# yacc1buss.net
KiCad netlist of a schematic drawn in EAGLE
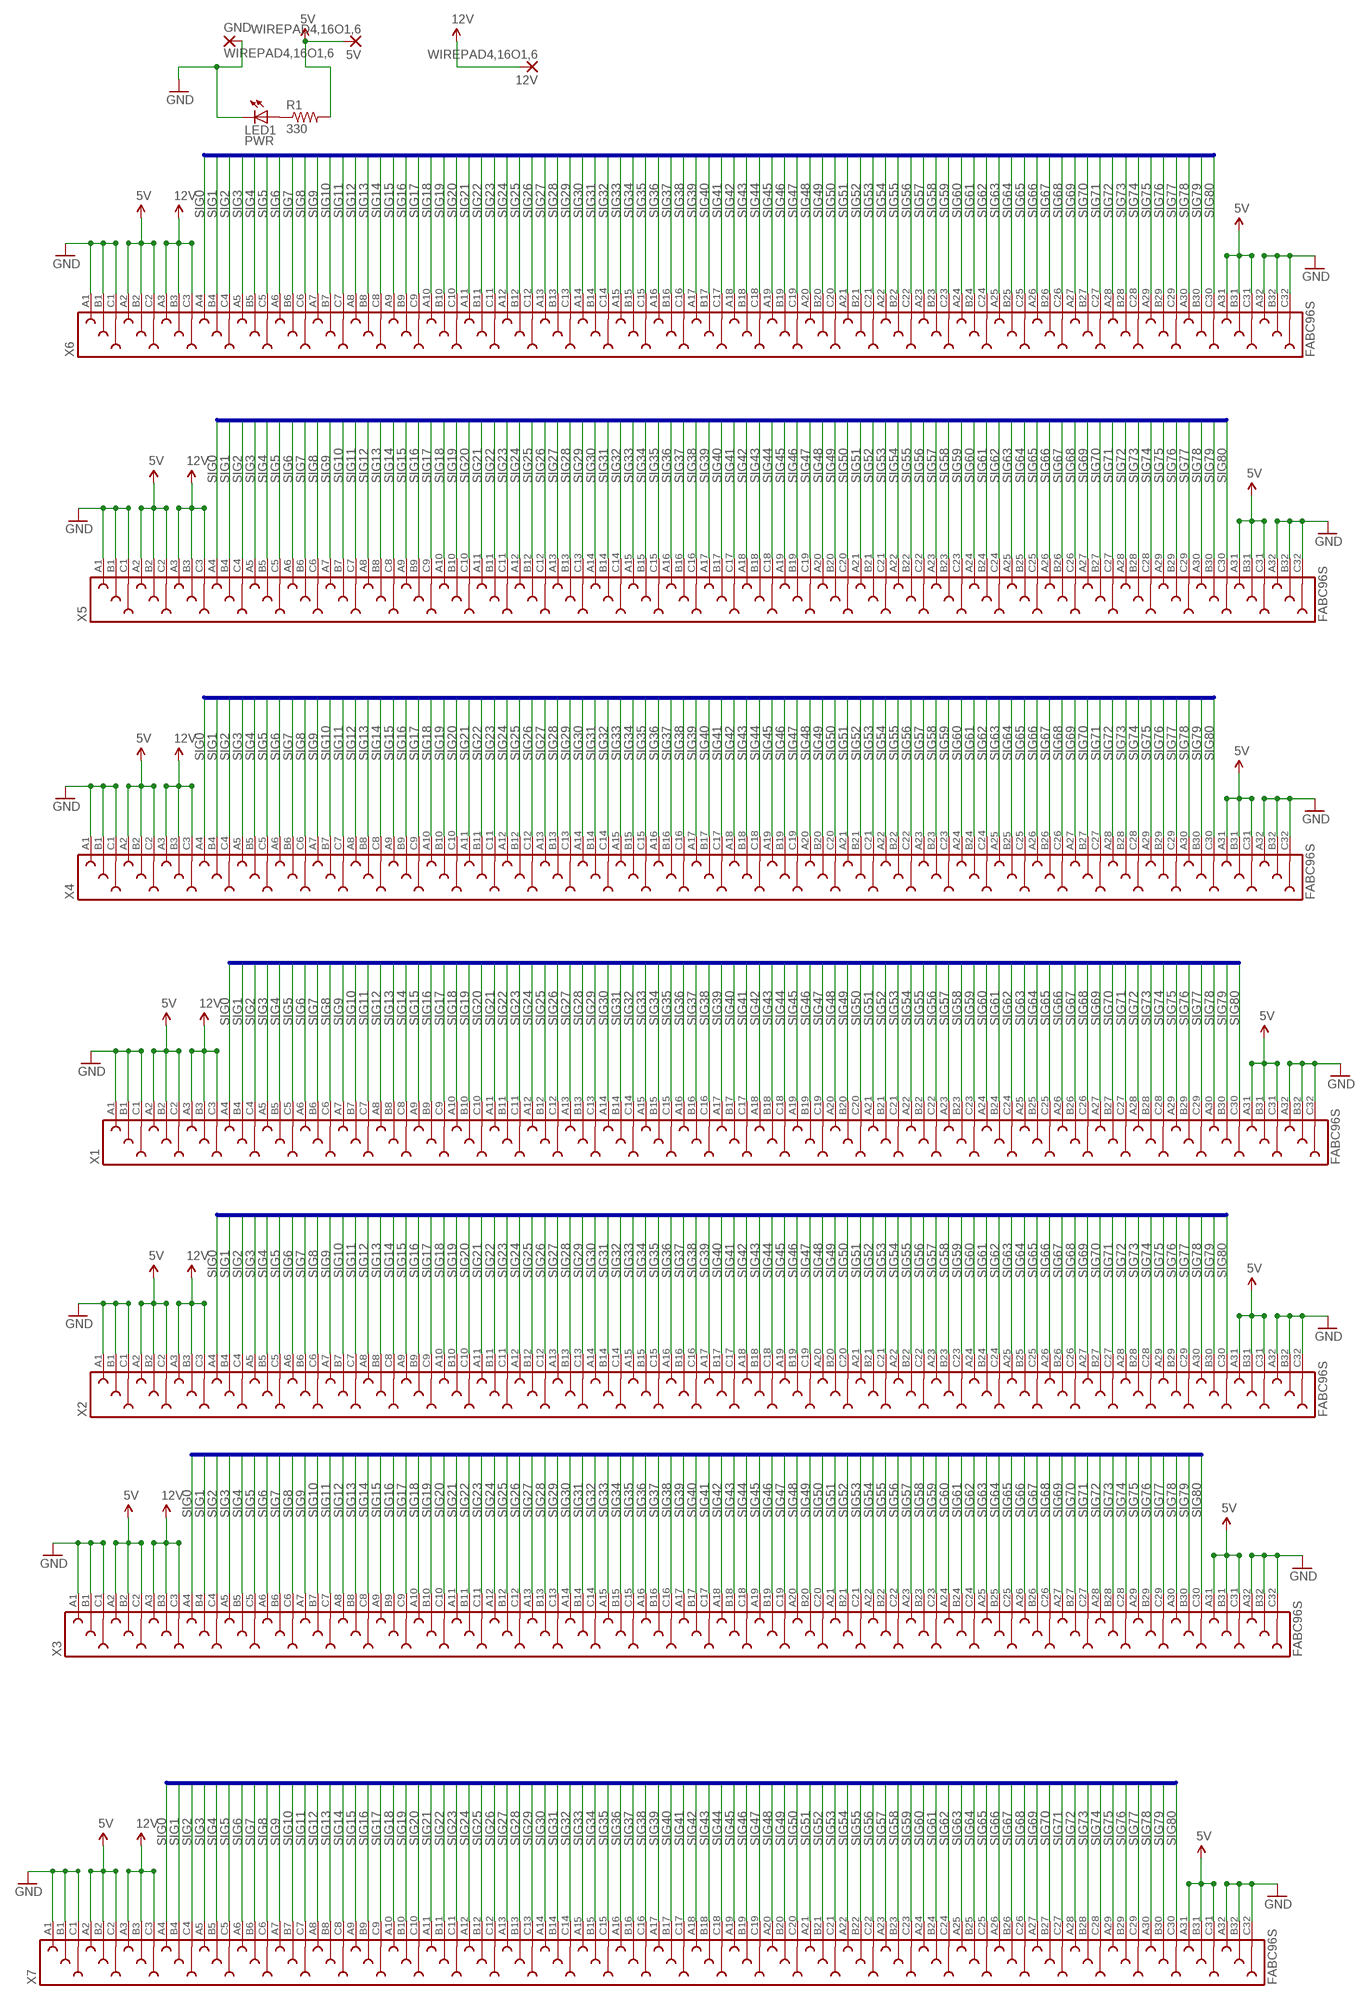
[diagram p0: schematic, sheet 1]

(export (version "E")
  (design (tool "Eeschema 10.0.6"))
  (components
    (comp (ref "5V")
      (value "WIREPAD4,16O1,6")
      (footprint "eagle-import:4,16O1,6")
      (libsource (lib "eagle-import") (part "WIREPAD4,16O1,6"))
    )
    (comp (ref "12V")
      (value "WIREPAD4,16O1,6")
      (footprint "eagle-import:4,16O1,6")
      (libsource (lib "eagle-import") (part "WIREPAD4,16O1,6"))
    )
    (comp (ref "GND")
      (value "WIREPAD4,16O1,6")
      (footprint "eagle-import:4,16O1,6")
      (libsource (lib "eagle-import") (part "WIREPAD4,16O1,6"))
    )
    (comp (ref "LED1")
      (value "PWR")
      (footprint "eagle-import:LED5MM")
      (libsource (lib "eagle-import") (part "LED5MM"))
    )
    (comp (ref "R1")
      (value "330")
      (footprint "eagle-import:0309_12")
      (libsource (lib "eagle-import") (part "R-US_0309/12"))
    )
    (comp (ref "X1")
      (value "FABC96S")
      (footprint "eagle-import:FABC96S")
      (libsource (lib "eagle-import") (part "FABC96S"))
    )
    (comp (ref "X2")
      (value "FABC96S")
      (footprint "eagle-import:FABC96S")
      (libsource (lib "eagle-import") (part "FABC96S"))
    )
    (comp (ref "X3")
      (value "FABC96S")
      (footprint "eagle-import:FABC96S")
      (libsource (lib "eagle-import") (part "FABC96S"))
    )
    (comp (ref "X4")
      (value "FABC96S")
      (footprint "eagle-import:FABC96S")
      (libsource (lib "eagle-import") (part "FABC96S"))
    )
    (comp (ref "X5")
      (value "FABC96S")
      (footprint "eagle-import:FABC96S")
      (libsource (lib "eagle-import") (part "FABC96S"))
    )
    (comp (ref "X6")
      (value "FABC96S")
      (footprint "eagle-import:FABC96S")
      (libsource (lib "eagle-import") (part "FABC96S"))
    )
    (comp (ref "X7")
      (value "FABC96S")
      (footprint "eagle-import:FABC96S")
      (libsource (lib "eagle-import") (part "FABC96S"))
    )
  )
  (nets
    (net (code "1") (name "/SIG0") (class "Default")
      (node (ref "X1") (pin "A4") (pinfunction "A4_A4") (pintype "passive"))
      (node (ref "X2") (pin "A4") (pinfunction "A4_A4") (pintype "passive"))
      (node (ref "X3") (pin "A4") (pinfunction "A4_A4") (pintype "passive"))
      (node (ref "X4") (pin "A4") (pinfunction "A4_A4") (pintype "passive"))
      (node (ref "X5") (pin "A4") (pinfunction "A4_A4") (pintype "passive"))
      (node (ref "X6") (pin "A4") (pinfunction "A4_A4") (pintype "passive"))
      (node (ref "X7") (pin "A4") (pinfunction "A4_A4") (pintype "passive"))
    )
    (net (code "2") (name "/SIG1") (class "Default")
      (node (ref "X1") (pin "B4") (pinfunction "B4_B4") (pintype "passive"))
      (node (ref "X2") (pin "B4") (pinfunction "B4_B4") (pintype "passive"))
      (node (ref "X3") (pin "B4") (pinfunction "B4_B4") (pintype "passive"))
      (node (ref "X4") (pin "B4") (pinfunction "B4_B4") (pintype "passive"))
      (node (ref "X5") (pin "B4") (pinfunction "B4_B4") (pintype "passive"))
      (node (ref "X6") (pin "B4") (pinfunction "B4_B4") (pintype "passive"))
      (node (ref "X7") (pin "B4") (pinfunction "B4_B4") (pintype "passive"))
    )
    (net (code "3") (name "/SIG2") (class "Default")
      (node (ref "X1") (pin "C4") (pinfunction "C4_C4") (pintype "passive"))
      (node (ref "X2") (pin "C4") (pinfunction "C4_C4") (pintype "passive"))
      (node (ref "X3") (pin "C4") (pinfunction "C4_C4") (pintype "passive"))
      (node (ref "X4") (pin "C4") (pinfunction "C4_C4") (pintype "passive"))
      (node (ref "X5") (pin "C4") (pinfunction "C4_C4") (pintype "passive"))
      (node (ref "X6") (pin "C4") (pinfunction "C4_C4") (pintype "passive"))
      (node (ref "X7") (pin "C4") (pinfunction "C4_C4") (pintype "passive"))
    )
    (net (code "4") (name "/SIG3") (class "Default")
      (node (ref "X1") (pin "A5") (pinfunction "A5_A5") (pintype "passive"))
      (node (ref "X2") (pin "A5") (pinfunction "A5_A5") (pintype "passive"))
      (node (ref "X3") (pin "A5") (pinfunction "A5_A5") (pintype "passive"))
      (node (ref "X4") (pin "A5") (pinfunction "A5_A5") (pintype "passive"))
      (node (ref "X5") (pin "A5") (pinfunction "A5_A5") (pintype "passive"))
      (node (ref "X6") (pin "A5") (pinfunction "A5_A5") (pintype "passive"))
      (node (ref "X7") (pin "A5") (pinfunction "A5_A5") (pintype "passive"))
    )
    (net (code "5") (name "/SIG4") (class "Default")
      (node (ref "X1") (pin "B5") (pinfunction "B5_B5") (pintype "passive"))
      (node (ref "X2") (pin "B5") (pinfunction "B5_B5") (pintype "passive"))
      (node (ref "X3") (pin "B5") (pinfunction "B5_B5") (pintype "passive"))
      (node (ref "X4") (pin "B5") (pinfunction "B5_B5") (pintype "passive"))
      (node (ref "X5") (pin "B5") (pinfunction "B5_B5") (pintype "passive"))
      (node (ref "X6") (pin "B5") (pinfunction "B5_B5") (pintype "passive"))
      (node (ref "X7") (pin "B5") (pinfunction "B5_B5") (pintype "passive"))
    )
    (net (code "6") (name "/SIG5") (class "Default")
      (node (ref "X1") (pin "C5") (pinfunction "C5_C5") (pintype "passive"))
      (node (ref "X2") (pin "C5") (pinfunction "C5_C5") (pintype "passive"))
      (node (ref "X3") (pin "C5") (pinfunction "C5_C5") (pintype "passive"))
      (node (ref "X4") (pin "C5") (pinfunction "C5_C5") (pintype "passive"))
      (node (ref "X5") (pin "C5") (pinfunction "C5_C5") (pintype "passive"))
      (node (ref "X6") (pin "C5") (pinfunction "C5_C5") (pintype "passive"))
      (node (ref "X7") (pin "C5") (pinfunction "C5_C5") (pintype "passive"))
    )
    (net (code "7") (name "/SIG6") (class "Default")
      (node (ref "X1") (pin "A6") (pinfunction "A6_A6") (pintype "passive"))
      (node (ref "X2") (pin "A6") (pinfunction "A6_A6") (pintype "passive"))
      (node (ref "X3") (pin "A6") (pinfunction "A6_A6") (pintype "passive"))
      (node (ref "X4") (pin "A6") (pinfunction "A6_A6") (pintype "passive"))
      (node (ref "X5") (pin "A6") (pinfunction "A6_A6") (pintype "passive"))
      (node (ref "X6") (pin "A6") (pinfunction "A6_A6") (pintype "passive"))
      (node (ref "X7") (pin "A6") (pinfunction "A6_A6") (pintype "passive"))
    )
    (net (code "8") (name "/SIG7") (class "Default")
      (node (ref "X1") (pin "B6") (pinfunction "B6_B6") (pintype "passive"))
      (node (ref "X2") (pin "B6") (pinfunction "B6_B6") (pintype "passive"))
      (node (ref "X3") (pin "B6") (pinfunction "B6_B6") (pintype "passive"))
      (node (ref "X4") (pin "B6") (pinfunction "B6_B6") (pintype "passive"))
      (node (ref "X5") (pin "B6") (pinfunction "B6_B6") (pintype "passive"))
      (node (ref "X6") (pin "B6") (pinfunction "B6_B6") (pintype "passive"))
      (node (ref "X7") (pin "B6") (pinfunction "B6_B6") (pintype "passive"))
    )
    (net (code "9") (name "/SIG8") (class "Default")
      (node (ref "X1") (pin "C6") (pinfunction "C6_C6") (pintype "passive"))
      (node (ref "X2") (pin "C6") (pinfunction "C6_C6") (pintype "passive"))
      (node (ref "X3") (pin "C6") (pinfunction "C6_C6") (pintype "passive"))
      (node (ref "X4") (pin "C6") (pinfunction "C6_C6") (pintype "passive"))
      (node (ref "X5") (pin "C6") (pinfunction "C6_C6") (pintype "passive"))
      (node (ref "X6") (pin "C6") (pinfunction "C6_C6") (pintype "passive"))
      (node (ref "X7") (pin "C6") (pinfunction "C6_C6") (pintype "passive"))
    )
    (net (code "10") (name "/SIG9") (class "Default")
      (node (ref "X1") (pin "A7") (pinfunction "A7_A7") (pintype "passive"))
      (node (ref "X2") (pin "A7") (pinfunction "A7_A7") (pintype "passive"))
      (node (ref "X3") (pin "A7") (pinfunction "A7_A7") (pintype "passive"))
      (node (ref "X4") (pin "A7") (pinfunction "A7_A7") (pintype "passive"))
      (node (ref "X5") (pin "A7") (pinfunction "A7_A7") (pintype "passive"))
      (node (ref "X6") (pin "A7") (pinfunction "A7_A7") (pintype "passive"))
      (node (ref "X7") (pin "A7") (pinfunction "A7_A7") (pintype "passive"))
    )
    (net (code "11") (name "/SIG10") (class "Default")
      (node (ref "X1") (pin "B7") (pinfunction "B7_B7") (pintype "passive"))
      (node (ref "X2") (pin "B7") (pinfunction "B7_B7") (pintype "passive"))
      (node (ref "X3") (pin "B7") (pinfunction "B7_B7") (pintype "passive"))
      (node (ref "X4") (pin "B7") (pinfunction "B7_B7") (pintype "passive"))
      (node (ref "X5") (pin "B7") (pinfunction "B7_B7") (pintype "passive"))
      (node (ref "X6") (pin "B7") (pinfunction "B7_B7") (pintype "passive"))
      (node (ref "X7") (pin "B7") (pinfunction "B7_B7") (pintype "passive"))
    )
    (net (code "12") (name "/SIG11") (class "Default")
      (node (ref "X1") (pin "C7") (pinfunction "C7_C7") (pintype "passive"))
      (node (ref "X2") (pin "C7") (pinfunction "C7_C7") (pintype "passive"))
      (node (ref "X3") (pin "C7") (pinfunction "C7_C7") (pintype "passive"))
      (node (ref "X4") (pin "C7") (pinfunction "C7_C7") (pintype "passive"))
      (node (ref "X5") (pin "C7") (pinfunction "C7_C7") (pintype "passive"))
      (node (ref "X6") (pin "C7") (pinfunction "C7_C7") (pintype "passive"))
      (node (ref "X7") (pin "C7") (pinfunction "C7_C7") (pintype "passive"))
    )
    (net (code "13") (name "/SIG12") (class "Default")
      (node (ref "X1") (pin "A8") (pinfunction "A8_A8") (pintype "passive"))
      (node (ref "X2") (pin "A8") (pinfunction "A8_A8") (pintype "passive"))
      (node (ref "X3") (pin "A8") (pinfunction "A8_A8") (pintype "passive"))
      (node (ref "X4") (pin "A8") (pinfunction "A8_A8") (pintype "passive"))
      (node (ref "X5") (pin "A8") (pinfunction "A8_A8") (pintype "passive"))
      (node (ref "X6") (pin "A8") (pinfunction "A8_A8") (pintype "passive"))
      (node (ref "X7") (pin "A8") (pinfunction "A8_A8") (pintype "passive"))
    )
    (net (code "14") (name "/SIG13") (class "Default")
      (node (ref "X1") (pin "B8") (pinfunction "B8_B8") (pintype "passive"))
      (node (ref "X2") (pin "B8") (pinfunction "B8_B8") (pintype "passive"))
      (node (ref "X3") (pin "B8") (pinfunction "B8_B8") (pintype "passive"))
      (node (ref "X4") (pin "B8") (pinfunction "B8_B8") (pintype "passive"))
      (node (ref "X5") (pin "B8") (pinfunction "B8_B8") (pintype "passive"))
      (node (ref "X6") (pin "B8") (pinfunction "B8_B8") (pintype "passive"))
      (node (ref "X7") (pin "B8") (pinfunction "B8_B8") (pintype "passive"))
    )
    (net (code "15") (name "/SIG14") (class "Default")
      (node (ref "X1") (pin "C8") (pinfunction "C8_C8") (pintype "passive"))
      (node (ref "X2") (pin "C8") (pinfunction "C8_C8") (pintype "passive"))
      (node (ref "X3") (pin "C8") (pinfunction "C8_C8") (pintype "passive"))
      (node (ref "X4") (pin "C8") (pinfunction "C8_C8") (pintype "passive"))
      (node (ref "X5") (pin "C8") (pinfunction "C8_C8") (pintype "passive"))
      (node (ref "X6") (pin "C8") (pinfunction "C8_C8") (pintype "passive"))
      (node (ref "X7") (pin "C8") (pinfunction "C8_C8") (pintype "passive"))
    )
    (net (code "16") (name "/SIG15") (class "Default")
      (node (ref "X1") (pin "A9") (pinfunction "A9_A9") (pintype "passive"))
      (node (ref "X2") (pin "A9") (pinfunction "A9_A9") (pintype "passive"))
      (node (ref "X3") (pin "A9") (pinfunction "A9_A9") (pintype "passive"))
      (node (ref "X4") (pin "A9") (pinfunction "A9_A9") (pintype "passive"))
      (node (ref "X5") (pin "A9") (pinfunction "A9_A9") (pintype "passive"))
      (node (ref "X6") (pin "A9") (pinfunction "A9_A9") (pintype "passive"))
      (node (ref "X7") (pin "A9") (pinfunction "A9_A9") (pintype "passive"))
    )
    (net (code "17") (name "/SIG16") (class "Default")
      (node (ref "X1") (pin "B9") (pinfunction "B9_B9") (pintype "passive"))
      (node (ref "X2") (pin "B9") (pinfunction "B9_B9") (pintype "passive"))
      (node (ref "X3") (pin "B9") (pinfunction "B9_B9") (pintype "passive"))
      (node (ref "X4") (pin "B9") (pinfunction "B9_B9") (pintype "passive"))
      (node (ref "X5") (pin "B9") (pinfunction "B9_B9") (pintype "passive"))
      (node (ref "X6") (pin "B9") (pinfunction "B9_B9") (pintype "passive"))
      (node (ref "X7") (pin "B9") (pinfunction "B9_B9") (pintype "passive"))
    )
    (net (code "18") (name "/SIG17") (class "Default")
      (node (ref "X1") (pin "C9") (pinfunction "C9_C9") (pintype "passive"))
      (node (ref "X2") (pin "C9") (pinfunction "C9_C9") (pintype "passive"))
      (node (ref "X3") (pin "C9") (pinfunction "C9_C9") (pintype "passive"))
      (node (ref "X4") (pin "C9") (pinfunction "C9_C9") (pintype "passive"))
      (node (ref "X5") (pin "C9") (pinfunction "C9_C9") (pintype "passive"))
      (node (ref "X6") (pin "C9") (pinfunction "C9_C9") (pintype "passive"))
      (node (ref "X7") (pin "C9") (pinfunction "C9_C9") (pintype "passive"))
    )
    (net (code "19") (name "/SIG18") (class "Default")
      (node (ref "X1") (pin "A10") (pinfunction "A10_A10") (pintype "passive"))
      (node (ref "X2") (pin "A10") (pinfunction "A10_A10") (pintype "passive"))
      (node (ref "X3") (pin "A10") (pinfunction "A10_A10") (pintype "passive"))
      (node (ref "X4") (pin "A10") (pinfunction "A10_A10") (pintype "passive"))
      (node (ref "X5") (pin "A10") (pinfunction "A10_A10") (pintype "passive"))
      (node (ref "X6") (pin "A10") (pinfunction "A10_A10") (pintype "passive"))
      (node (ref "X7") (pin "A10") (pinfunction "A10_A10") (pintype "passive"))
    )
    (net (code "20") (name "/SIG19") (class "Default")
      (node (ref "X1") (pin "B10") (pinfunction "B10_B10") (pintype "passive"))
      (node (ref "X2") (pin "B10") (pinfunction "B10_B10") (pintype "passive"))
      (node (ref "X3") (pin "B10") (pinfunction "B10_B10") (pintype "passive"))
      (node (ref "X4") (pin "B10") (pinfunction "B10_B10") (pintype "passive"))
      (node (ref "X5") (pin "B10") (pinfunction "B10_B10") (pintype "passive"))
      (node (ref "X6") (pin "B10") (pinfunction "B10_B10") (pintype "passive"))
      (node (ref "X7") (pin "B10") (pinfunction "B10_B10") (pintype "passive"))
    )
    (net (code "21") (name "/SIG20") (class "Default")
      (node (ref "X1") (pin "C10") (pinfunction "C10_C10") (pintype "passive"))
      (node (ref "X2") (pin "C10") (pinfunction "C10_C10") (pintype "passive"))
      (node (ref "X3") (pin "C10") (pinfunction "C10_C10") (pintype "passive"))
      (node (ref "X4") (pin "C10") (pinfunction "C10_C10") (pintype "passive"))
      (node (ref "X5") (pin "C10") (pinfunction "C10_C10") (pintype "passive"))
      (node (ref "X6") (pin "C10") (pinfunction "C10_C10") (pintype "passive"))
      (node (ref "X7") (pin "C10") (pinfunction "C10_C10") (pintype "passive"))
    )
    (net (code "22") (name "/SIG21") (class "Default")
      (node (ref "X1") (pin "A11") (pinfunction "A11_A11") (pintype "passive"))
      (node (ref "X2") (pin "A11") (pinfunction "A11_A11") (pintype "passive"))
      (node (ref "X3") (pin "A11") (pinfunction "A11_A11") (pintype "passive"))
      (node (ref "X4") (pin "A11") (pinfunction "A11_A11") (pintype "passive"))
      (node (ref "X5") (pin "A11") (pinfunction "A11_A11") (pintype "passive"))
      (node (ref "X6") (pin "A11") (pinfunction "A11_A11") (pintype "passive"))
      (node (ref "X7") (pin "A11") (pinfunction "A11_A11") (pintype "passive"))
    )
    (net (code "23") (name "/SIG22") (class "Default")
      (node (ref "X1") (pin "B11") (pinfunction "B11_B11") (pintype "passive"))
      (node (ref "X2") (pin "B11") (pinfunction "B11_B11") (pintype "passive"))
      (node (ref "X3") (pin "B11") (pinfunction "B11_B11") (pintype "passive"))
      (node (ref "X4") (pin "B11") (pinfunction "B11_B11") (pintype "passive"))
      (node (ref "X5") (pin "B11") (pinfunction "B11_B11") (pintype "passive"))
      (node (ref "X6") (pin "B11") (pinfunction "B11_B11") (pintype "passive"))
      (node (ref "X7") (pin "B11") (pinfunction "B11_B11") (pintype "passive"))
    )
    (net (code "24") (name "/SIG23") (class "Default")
      (node (ref "X1") (pin "C11") (pinfunction "C11_C11") (pintype "passive"))
      (node (ref "X2") (pin "C11") (pinfunction "C11_C11") (pintype "passive"))
      (node (ref "X3") (pin "C11") (pinfunction "C11_C11") (pintype "passive"))
      (node (ref "X4") (pin "C11") (pinfunction "C11_C11") (pintype "passive"))
      (node (ref "X5") (pin "C11") (pinfunction "C11_C11") (pintype "passive"))
      (node (ref "X6") (pin "C11") (pinfunction "C11_C11") (pintype "passive"))
      (node (ref "X7") (pin "C11") (pinfunction "C11_C11") (pintype "passive"))
    )
    (net (code "25") (name "/SIG24") (class "Default")
      (node (ref "X1") (pin "A12") (pinfunction "A12_A12") (pintype "passive"))
      (node (ref "X2") (pin "A12") (pinfunction "A12_A12") (pintype "passive"))
      (node (ref "X3") (pin "A12") (pinfunction "A12_A12") (pintype "passive"))
      (node (ref "X4") (pin "A12") (pinfunction "A12_A12") (pintype "passive"))
      (node (ref "X5") (pin "A12") (pinfunction "A12_A12") (pintype "passive"))
      (node (ref "X6") (pin "A12") (pinfunction "A12_A12") (pintype "passive"))
      (node (ref "X7") (pin "A12") (pinfunction "A12_A12") (pintype "passive"))
    )
    (net (code "26") (name "/SIG25") (class "Default")
      (node (ref "X1") (pin "B12") (pinfunction "B12_B12") (pintype "passive"))
      (node (ref "X2") (pin "B12") (pinfunction "B12_B12") (pintype "passive"))
      (node (ref "X3") (pin "B12") (pinfunction "B12_B12") (pintype "passive"))
      (node (ref "X4") (pin "B12") (pinfunction "B12_B12") (pintype "passive"))
      (node (ref "X5") (pin "B12") (pinfunction "B12_B12") (pintype "passive"))
      (node (ref "X6") (pin "B12") (pinfunction "B12_B12") (pintype "passive"))
      (node (ref "X7") (pin "B12") (pinfunction "B12_B12") (pintype "passive"))
    )
    (net (code "27") (name "/SIG26") (class "Default")
      (node (ref "X1") (pin "C12") (pinfunction "C12_C12") (pintype "passive"))
      (node (ref "X2") (pin "C12") (pinfunction "C12_C12") (pintype "passive"))
      (node (ref "X3") (pin "C12") (pinfunction "C12_C12") (pintype "passive"))
      (node (ref "X4") (pin "C12") (pinfunction "C12_C12") (pintype "passive"))
      (node (ref "X5") (pin "C12") (pinfunction "C12_C12") (pintype "passive"))
      (node (ref "X6") (pin "C12") (pinfunction "C12_C12") (pintype "passive"))
      (node (ref "X7") (pin "C12") (pinfunction "C12_C12") (pintype "passive"))
    )
    (net (code "28") (name "/SIG27") (class "Default")
      (node (ref "X1") (pin "A13") (pinfunction "A13_A13") (pintype "passive"))
      (node (ref "X2") (pin "A13") (pinfunction "A13_A13") (pintype "passive"))
      (node (ref "X3") (pin "A13") (pinfunction "A13_A13") (pintype "passive"))
      (node (ref "X4") (pin "A13") (pinfunction "A13_A13") (pintype "passive"))
      (node (ref "X5") (pin "A13") (pinfunction "A13_A13") (pintype "passive"))
      (node (ref "X6") (pin "A13") (pinfunction "A13_A13") (pintype "passive"))
      (node (ref "X7") (pin "A13") (pinfunction "A13_A13") (pintype "passive"))
    )
    (net (code "29") (name "/SIG28") (class "Default")
      (node (ref "X1") (pin "B13") (pinfunction "B13_B13") (pintype "passive"))
      (node (ref "X2") (pin "B13") (pinfunction "B13_B13") (pintype "passive"))
      (node (ref "X3") (pin "B13") (pinfunction "B13_B13") (pintype "passive"))
      (node (ref "X4") (pin "B13") (pinfunction "B13_B13") (pintype "passive"))
      (node (ref "X5") (pin "B13") (pinfunction "B13_B13") (pintype "passive"))
      (node (ref "X6") (pin "B13") (pinfunction "B13_B13") (pintype "passive"))
      (node (ref "X7") (pin "B13") (pinfunction "B13_B13") (pintype "passive"))
    )
    (net (code "30") (name "/SIG29") (class "Default")
      (node (ref "X1") (pin "C13") (pinfunction "C13_C13") (pintype "passive"))
      (node (ref "X2") (pin "C13") (pinfunction "C13_C13") (pintype "passive"))
      (node (ref "X3") (pin "C13") (pinfunction "C13_C13") (pintype "passive"))
      (node (ref "X4") (pin "C13") (pinfunction "C13_C13") (pintype "passive"))
      (node (ref "X5") (pin "C13") (pinfunction "C13_C13") (pintype "passive"))
      (node (ref "X6") (pin "C13") (pinfunction "C13_C13") (pintype "passive"))
      (node (ref "X7") (pin "C13") (pinfunction "C13_C13") (pintype "passive"))
    )
    (net (code "31") (name "/SIG30") (class "Default")
      (node (ref "X1") (pin "A14") (pinfunction "A14_A14") (pintype "passive"))
      (node (ref "X2") (pin "A14") (pinfunction "A14_A14") (pintype "passive"))
      (node (ref "X3") (pin "A14") (pinfunction "A14_A14") (pintype "passive"))
      (node (ref "X4") (pin "A14") (pinfunction "A14_A14") (pintype "passive"))
      (node (ref "X5") (pin "A14") (pinfunction "A14_A14") (pintype "passive"))
      (node (ref "X6") (pin "A14") (pinfunction "A14_A14") (pintype "passive"))
      (node (ref "X7") (pin "A14") (pinfunction "A14_A14") (pintype "passive"))
    )
    (net (code "32") (name "/SIG31") (class "Default")
      (node (ref "X1") (pin "B14") (pinfunction "B14_B14") (pintype "passive"))
      (node (ref "X2") (pin "B14") (pinfunction "B14_B14") (pintype "passive"))
      (node (ref "X3") (pin "B14") (pinfunction "B14_B14") (pintype "passive"))
      (node (ref "X4") (pin "B14") (pinfunction "B14_B14") (pintype "passive"))
      (node (ref "X5") (pin "B14") (pinfunction "B14_B14") (pintype "passive"))
      (node (ref "X6") (pin "B14") (pinfunction "B14_B14") (pintype "passive"))
      (node (ref "X7") (pin "B14") (pinfunction "B14_B14") (pintype "passive"))
    )
    (net (code "33") (name "/SIG32") (class "Default")
      (node (ref "X1") (pin "C14") (pinfunction "C14_C14") (pintype "passive"))
      (node (ref "X2") (pin "C14") (pinfunction "C14_C14") (pintype "passive"))
      (node (ref "X3") (pin "C14") (pinfunction "C14_C14") (pintype "passive"))
      (node (ref "X4") (pin "C14") (pinfunction "C14_C14") (pintype "passive"))
      (node (ref "X5") (pin "C14") (pinfunction "C14_C14") (pintype "passive"))
      (node (ref "X6") (pin "C14") (pinfunction "C14_C14") (pintype "passive"))
      (node (ref "X7") (pin "C14") (pinfunction "C14_C14") (pintype "passive"))
    )
    (net (code "34") (name "/SIG33") (class "Default")
      (node (ref "X1") (pin "A15") (pinfunction "A15_A15") (pintype "passive"))
      (node (ref "X2") (pin "A15") (pinfunction "A15_A15") (pintype "passive"))
      (node (ref "X3") (pin "A15") (pinfunction "A15_A15") (pintype "passive"))
      (node (ref "X4") (pin "A15") (pinfunction "A15_A15") (pintype "passive"))
      (node (ref "X5") (pin "A15") (pinfunction "A15_A15") (pintype "passive"))
      (node (ref "X6") (pin "A15") (pinfunction "A15_A15") (pintype "passive"))
      (node (ref "X7") (pin "A15") (pinfunction "A15_A15") (pintype "passive"))
    )
    (net (code "35") (name "/SIG34") (class "Default")
      (node (ref "X1") (pin "B15") (pinfunction "B15_B15") (pintype "passive"))
      (node (ref "X2") (pin "B15") (pinfunction "B15_B15") (pintype "passive"))
      (node (ref "X3") (pin "B15") (pinfunction "B15_B15") (pintype "passive"))
      (node (ref "X4") (pin "B15") (pinfunction "B15_B15") (pintype "passive"))
      (node (ref "X5") (pin "B15") (pinfunction "B15_B15") (pintype "passive"))
      (node (ref "X6") (pin "B15") (pinfunction "B15_B15") (pintype "passive"))
      (node (ref "X7") (pin "B15") (pinfunction "B15_B15") (pintype "passive"))
    )
    (net (code "36") (name "/SIG35") (class "Default")
      (node (ref "X1") (pin "C15") (pinfunction "C15_C15") (pintype "passive"))
      (node (ref "X2") (pin "C15") (pinfunction "C15_C15") (pintype "passive"))
      (node (ref "X3") (pin "C15") (pinfunction "C15_C15") (pintype "passive"))
      (node (ref "X4") (pin "C15") (pinfunction "C15_C15") (pintype "passive"))
      (node (ref "X5") (pin "C15") (pinfunction "C15_C15") (pintype "passive"))
      (node (ref "X6") (pin "C15") (pinfunction "C15_C15") (pintype "passive"))
      (node (ref "X7") (pin "C15") (pinfunction "C15_C15") (pintype "passive"))
    )
    (net (code "37") (name "/SIG36") (class "Default")
      (node (ref "X1") (pin "A16") (pinfunction "A16_A16") (pintype "passive"))
      (node (ref "X2") (pin "A16") (pinfunction "A16_A16") (pintype "passive"))
      (node (ref "X3") (pin "A16") (pinfunction "A16_A16") (pintype "passive"))
      (node (ref "X4") (pin "A16") (pinfunction "A16_A16") (pintype "passive"))
      (node (ref "X5") (pin "A16") (pinfunction "A16_A16") (pintype "passive"))
      (node (ref "X6") (pin "A16") (pinfunction "A16_A16") (pintype "passive"))
      (node (ref "X7") (pin "A16") (pinfunction "A16_A16") (pintype "passive"))
    )
    (net (code "38") (name "/SIG37") (class "Default")
      (node (ref "X1") (pin "B16") (pinfunction "B16_B16") (pintype "passive"))
      (node (ref "X2") (pin "B16") (pinfunction "B16_B16") (pintype "passive"))
      (node (ref "X3") (pin "B16") (pinfunction "B16_B16") (pintype "passive"))
      (node (ref "X4") (pin "B16") (pinfunction "B16_B16") (pintype "passive"))
      (node (ref "X5") (pin "B16") (pinfunction "B16_B16") (pintype "passive"))
      (node (ref "X6") (pin "B16") (pinfunction "B16_B16") (pintype "passive"))
      (node (ref "X7") (pin "B16") (pinfunction "B16_B16") (pintype "passive"))
    )
    (net (code "39") (name "/SIG38") (class "Default")
      (node (ref "X1") (pin "C16") (pinfunction "C16_C16") (pintype "passive"))
      (node (ref "X2") (pin "C16") (pinfunction "C16_C16") (pintype "passive"))
      (node (ref "X3") (pin "C16") (pinfunction "C16_C16") (pintype "passive"))
      (node (ref "X4") (pin "C16") (pinfunction "C16_C16") (pintype "passive"))
      (node (ref "X5") (pin "C16") (pinfunction "C16_C16") (pintype "passive"))
      (node (ref "X6") (pin "C16") (pinfunction "C16_C16") (pintype "passive"))
      (node (ref "X7") (pin "C16") (pinfunction "C16_C16") (pintype "passive"))
    )
    (net (code "40") (name "/SIG39") (class "Default")
      (node (ref "X1") (pin "A17") (pinfunction "A17_A17") (pintype "passive"))
      (node (ref "X2") (pin "A17") (pinfunction "A17_A17") (pintype "passive"))
      (node (ref "X3") (pin "A17") (pinfunction "A17_A17") (pintype "passive"))
      (node (ref "X4") (pin "A17") (pinfunction "A17_A17") (pintype "passive"))
      (node (ref "X5") (pin "A17") (pinfunction "A17_A17") (pintype "passive"))
      (node (ref "X6") (pin "A17") (pinfunction "A17_A17") (pintype "passive"))
      (node (ref "X7") (pin "A17") (pinfunction "A17_A17") (pintype "passive"))
    )
    (net (code "41") (name "/SIG40") (class "Default")
      (node (ref "X1") (pin "B17") (pinfunction "B17_B17") (pintype "passive"))
      (node (ref "X2") (pin "B17") (pinfunction "B17_B17") (pintype "passive"))
      (node (ref "X3") (pin "B17") (pinfunction "B17_B17") (pintype "passive"))
      (node (ref "X4") (pin "B17") (pinfunction "B17_B17") (pintype "passive"))
      (node (ref "X5") (pin "B17") (pinfunction "B17_B17") (pintype "passive"))
      (node (ref "X6") (pin "B17") (pinfunction "B17_B17") (pintype "passive"))
      (node (ref "X7") (pin "B17") (pinfunction "B17_B17") (pintype "passive"))
    )
    (net (code "42") (name "/SIG41") (class "Default")
      (node (ref "X1") (pin "C17") (pinfunction "C17_C17") (pintype "passive"))
      (node (ref "X2") (pin "C17") (pinfunction "C17_C17") (pintype "passive"))
      (node (ref "X3") (pin "C17") (pinfunction "C17_C17") (pintype "passive"))
      (node (ref "X4") (pin "C17") (pinfunction "C17_C17") (pintype "passive"))
      (node (ref "X5") (pin "C17") (pinfunction "C17_C17") (pintype "passive"))
      (node (ref "X6") (pin "C17") (pinfunction "C17_C17") (pintype "passive"))
      (node (ref "X7") (pin "C17") (pinfunction "C17_C17") (pintype "passive"))
    )
    (net (code "43") (name "/SIG42") (class "Default")
      (node (ref "X1") (pin "A18") (pinfunction "A18_A18") (pintype "passive"))
      (node (ref "X2") (pin "A18") (pinfunction "A18_A18") (pintype "passive"))
      (node (ref "X3") (pin "A18") (pinfunction "A18_A18") (pintype "passive"))
      (node (ref "X4") (pin "A18") (pinfunction "A18_A18") (pintype "passive"))
      (node (ref "X5") (pin "A18") (pinfunction "A18_A18") (pintype "passive"))
      (node (ref "X6") (pin "A18") (pinfunction "A18_A18") (pintype "passive"))
      (node (ref "X7") (pin "A18") (pinfunction "A18_A18") (pintype "passive"))
    )
    (net (code "44") (name "/SIG43") (class "Default")
      (node (ref "X1") (pin "B18") (pinfunction "B18_B18") (pintype "passive"))
      (node (ref "X2") (pin "B18") (pinfunction "B18_B18") (pintype "passive"))
      (node (ref "X3") (pin "B18") (pinfunction "B18_B18") (pintype "passive"))
      (node (ref "X4") (pin "B18") (pinfunction "B18_B18") (pintype "passive"))
      (node (ref "X5") (pin "B18") (pinfunction "B18_B18") (pintype "passive"))
      (node (ref "X6") (pin "B18") (pinfunction "B18_B18") (pintype "passive"))
      (node (ref "X7") (pin "B18") (pinfunction "B18_B18") (pintype "passive"))
    )
    (net (code "45") (name "/SIG44") (class "Default")
      (node (ref "X1") (pin "C18") (pinfunction "C18_C18") (pintype "passive"))
      (node (ref "X2") (pin "C18") (pinfunction "C18_C18") (pintype "passive"))
      (node (ref "X3") (pin "C18") (pinfunction "C18_C18") (pintype "passive"))
      (node (ref "X4") (pin "C18") (pinfunction "C18_C18") (pintype "passive"))
      (node (ref "X5") (pin "C18") (pinfunction "C18_C18") (pintype "passive"))
      (node (ref "X6") (pin "C18") (pinfunction "C18_C18") (pintype "passive"))
      (node (ref "X7") (pin "C18") (pinfunction "C18_C18") (pintype "passive"))
    )
    (net (code "46") (name "/SIG45") (class "Default")
      (node (ref "X1") (pin "A19") (pinfunction "A19_A19") (pintype "passive"))
      (node (ref "X2") (pin "A19") (pinfunction "A19_A19") (pintype "passive"))
      (node (ref "X3") (pin "A19") (pinfunction "A19_A19") (pintype "passive"))
      (node (ref "X4") (pin "A19") (pinfunction "A19_A19") (pintype "passive"))
      (node (ref "X5") (pin "A19") (pinfunction "A19_A19") (pintype "passive"))
      (node (ref "X6") (pin "A19") (pinfunction "A19_A19") (pintype "passive"))
      (node (ref "X7") (pin "A19") (pinfunction "A19_A19") (pintype "passive"))
    )
    (net (code "47") (name "/SIG46") (class "Default")
      (node (ref "X1") (pin "B19") (pinfunction "B19_B19") (pintype "passive"))
      (node (ref "X2") (pin "B19") (pinfunction "B19_B19") (pintype "passive"))
      (node (ref "X3") (pin "B19") (pinfunction "B19_B19") (pintype "passive"))
      (node (ref "X4") (pin "B19") (pinfunction "B19_B19") (pintype "passive"))
      (node (ref "X5") (pin "B19") (pinfunction "B19_B19") (pintype "passive"))
      (node (ref "X6") (pin "B19") (pinfunction "B19_B19") (pintype "passive"))
      (node (ref "X7") (pin "B19") (pinfunction "B19_B19") (pintype "passive"))
    )
    (net (code "48") (name "/SIG47") (class "Default")
      (node (ref "X1") (pin "C19") (pinfunction "C19_C19") (pintype "passive"))
      (node (ref "X2") (pin "C19") (pinfunction "C19_C19") (pintype "passive"))
      (node (ref "X3") (pin "C19") (pinfunction "C19_C19") (pintype "passive"))
      (node (ref "X4") (pin "C19") (pinfunction "C19_C19") (pintype "passive"))
      (node (ref "X5") (pin "C19") (pinfunction "C19_C19") (pintype "passive"))
      (node (ref "X6") (pin "C19") (pinfunction "C19_C19") (pintype "passive"))
      (node (ref "X7") (pin "C19") (pinfunction "C19_C19") (pintype "passive"))
    )
    (net (code "49") (name "/SIG48") (class "Default")
      (node (ref "X1") (pin "A20") (pinfunction "A20_A20") (pintype "passive"))
      (node (ref "X2") (pin "A20") (pinfunction "A20_A20") (pintype "passive"))
      (node (ref "X3") (pin "A20") (pinfunction "A20_A20") (pintype "passive"))
      (node (ref "X4") (pin "A20") (pinfunction "A20_A20") (pintype "passive"))
      (node (ref "X5") (pin "A20") (pinfunction "A20_A20") (pintype "passive"))
      (node (ref "X6") (pin "A20") (pinfunction "A20_A20") (pintype "passive"))
      (node (ref "X7") (pin "A20") (pinfunction "A20_A20") (pintype "passive"))
    )
    (net (code "50") (name "/SIG49") (class "Default")
      (node (ref "X1") (pin "B20") (pinfunction "B20_B20") (pintype "passive"))
      (node (ref "X2") (pin "B20") (pinfunction "B20_B20") (pintype "passive"))
      (node (ref "X3") (pin "B20") (pinfunction "B20_B20") (pintype "passive"))
      (node (ref "X4") (pin "B20") (pinfunction "B20_B20") (pintype "passive"))
      (node (ref "X5") (pin "B20") (pinfunction "B20_B20") (pintype "passive"))
      (node (ref "X6") (pin "B20") (pinfunction "B20_B20") (pintype "passive"))
      (node (ref "X7") (pin "B20") (pinfunction "B20_B20") (pintype "passive"))
    )
    (net (code "51") (name "/SIG50") (class "Default")
      (node (ref "X1") (pin "C20") (pinfunction "C20_C20") (pintype "passive"))
      (node (ref "X2") (pin "C20") (pinfunction "C20_C20") (pintype "passive"))
      (node (ref "X3") (pin "C20") (pinfunction "C20_C20") (pintype "passive"))
      (node (ref "X4") (pin "C20") (pinfunction "C20_C20") (pintype "passive"))
      (node (ref "X5") (pin "C20") (pinfunction "C20_C20") (pintype "passive"))
      (node (ref "X6") (pin "C20") (pinfunction "C20_C20") (pintype "passive"))
      (node (ref "X7") (pin "C20") (pinfunction "C20_C20") (pintype "passive"))
    )
    (net (code "52") (name "/SIG51") (class "Default")
      (node (ref "X1") (pin "A21") (pinfunction "A21_A21") (pintype "passive"))
      (node (ref "X2") (pin "A21") (pinfunction "A21_A21") (pintype "passive"))
      (node (ref "X3") (pin "A21") (pinfunction "A21_A21") (pintype "passive"))
      (node (ref "X4") (pin "A21") (pinfunction "A21_A21") (pintype "passive"))
      (node (ref "X5") (pin "A21") (pinfunction "A21_A21") (pintype "passive"))
      (node (ref "X6") (pin "A21") (pinfunction "A21_A21") (pintype "passive"))
      (node (ref "X7") (pin "A21") (pinfunction "A21_A21") (pintype "passive"))
    )
    (net (code "53") (name "/SIG52") (class "Default")
      (node (ref "X1") (pin "B21") (pinfunction "B21_B21") (pintype "passive"))
      (node (ref "X2") (pin "B21") (pinfunction "B21_B21") (pintype "passive"))
      (node (ref "X3") (pin "B21") (pinfunction "B21_B21") (pintype "passive"))
      (node (ref "X4") (pin "B21") (pinfunction "B21_B21") (pintype "passive"))
      (node (ref "X5") (pin "B21") (pinfunction "B21_B21") (pintype "passive"))
      (node (ref "X6") (pin "B21") (pinfunction "B21_B21") (pintype "passive"))
      (node (ref "X7") (pin "B21") (pinfunction "B21_B21") (pintype "passive"))
    )
    (net (code "54") (name "/SIG53") (class "Default")
      (node (ref "X1") (pin "C21") (pinfunction "C21_C21") (pintype "passive"))
      (node (ref "X2") (pin "C21") (pinfunction "C21_C21") (pintype "passive"))
      (node (ref "X3") (pin "C21") (pinfunction "C21_C21") (pintype "passive"))
      (node (ref "X4") (pin "C21") (pinfunction "C21_C21") (pintype "passive"))
      (node (ref "X5") (pin "C21") (pinfunction "C21_C21") (pintype "passive"))
      (node (ref "X6") (pin "C21") (pinfunction "C21_C21") (pintype "passive"))
      (node (ref "X7") (pin "C21") (pinfunction "C21_C21") (pintype "passive"))
    )
    (net (code "55") (name "/SIG54") (class "Default")
      (node (ref "X1") (pin "A22") (pinfunction "A22_A22") (pintype "passive"))
      (node (ref "X2") (pin "A22") (pinfunction "A22_A22") (pintype "passive"))
      (node (ref "X3") (pin "A22") (pinfunction "A22_A22") (pintype "passive"))
      (node (ref "X4") (pin "A22") (pinfunction "A22_A22") (pintype "passive"))
      (node (ref "X5") (pin "A22") (pinfunction "A22_A22") (pintype "passive"))
      (node (ref "X6") (pin "A22") (pinfunction "A22_A22") (pintype "passive"))
      (node (ref "X7") (pin "A22") (pinfunction "A22_A22") (pintype "passive"))
    )
    (net (code "56") (name "/SIG55") (class "Default")
      (node (ref "X1") (pin "B22") (pinfunction "B22_B22") (pintype "passive"))
      (node (ref "X2") (pin "B22") (pinfunction "B22_B22") (pintype "passive"))
      (node (ref "X3") (pin "B22") (pinfunction "B22_B22") (pintype "passive"))
      (node (ref "X4") (pin "B22") (pinfunction "B22_B22") (pintype "passive"))
      (node (ref "X5") (pin "B22") (pinfunction "B22_B22") (pintype "passive"))
      (node (ref "X6") (pin "B22") (pinfunction "B22_B22") (pintype "passive"))
      (node (ref "X7") (pin "B22") (pinfunction "B22_B22") (pintype "passive"))
    )
    (net (code "57") (name "/SIG56") (class "Default")
      (node (ref "X1") (pin "C22") (pinfunction "C22_C22") (pintype "passive"))
      (node (ref "X2") (pin "C22") (pinfunction "C22_C22") (pintype "passive"))
      (node (ref "X3") (pin "C22") (pinfunction "C22_C22") (pintype "passive"))
      (node (ref "X4") (pin "C22") (pinfunction "C22_C22") (pintype "passive"))
      (node (ref "X5") (pin "C22") (pinfunction "C22_C22") (pintype "passive"))
      (node (ref "X6") (pin "C22") (pinfunction "C22_C22") (pintype "passive"))
      (node (ref "X7") (pin "C22") (pinfunction "C22_C22") (pintype "passive"))
    )
    (net (code "58") (name "/SIG57") (class "Default")
      (node (ref "X1") (pin "A23") (pinfunction "A23_A23") (pintype "passive"))
      (node (ref "X2") (pin "A23") (pinfunction "A23_A23") (pintype "passive"))
      (node (ref "X3") (pin "A23") (pinfunction "A23_A23") (pintype "passive"))
      (node (ref "X4") (pin "A23") (pinfunction "A23_A23") (pintype "passive"))
      (node (ref "X5") (pin "A23") (pinfunction "A23_A23") (pintype "passive"))
      (node (ref "X6") (pin "A23") (pinfunction "A23_A23") (pintype "passive"))
      (node (ref "X7") (pin "A23") (pinfunction "A23_A23") (pintype "passive"))
    )
    (net (code "59") (name "/SIG58") (class "Default")
      (node (ref "X1") (pin "B23") (pinfunction "B23_B23") (pintype "passive"))
      (node (ref "X2") (pin "B23") (pinfunction "B23_B23") (pintype "passive"))
      (node (ref "X3") (pin "B23") (pinfunction "B23_B23") (pintype "passive"))
      (node (ref "X4") (pin "B23") (pinfunction "B23_B23") (pintype "passive"))
      (node (ref "X5") (pin "B23") (pinfunction "B23_B23") (pintype "passive"))
      (node (ref "X6") (pin "B23") (pinfunction "B23_B23") (pintype "passive"))
      (node (ref "X7") (pin "B23") (pinfunction "B23_B23") (pintype "passive"))
    )
    (net (code "60") (name "/SIG59") (class "Default")
      (node (ref "X1") (pin "C23") (pinfunction "C23_C23") (pintype "passive"))
      (node (ref "X2") (pin "C23") (pinfunction "C23_C23") (pintype "passive"))
      (node (ref "X3") (pin "C23") (pinfunction "C23_C23") (pintype "passive"))
      (node (ref "X4") (pin "C23") (pinfunction "C23_C23") (pintype "passive"))
      (node (ref "X5") (pin "C23") (pinfunction "C23_C23") (pintype "passive"))
      (node (ref "X6") (pin "C23") (pinfunction "C23_C23") (pintype "passive"))
      (node (ref "X7") (pin "C23") (pinfunction "C23_C23") (pintype "passive"))
    )
    (net (code "61") (name "/SIG60") (class "Default")
      (node (ref "X1") (pin "A24") (pinfunction "A24_A24") (pintype "passive"))
      (node (ref "X2") (pin "A24") (pinfunction "A24_A24") (pintype "passive"))
      (node (ref "X3") (pin "A24") (pinfunction "A24_A24") (pintype "passive"))
      (node (ref "X4") (pin "A24") (pinfunction "A24_A24") (pintype "passive"))
      (node (ref "X5") (pin "A24") (pinfunction "A24_A24") (pintype "passive"))
      (node (ref "X6") (pin "A24") (pinfunction "A24_A24") (pintype "passive"))
      (node (ref "X7") (pin "A24") (pinfunction "A24_A24") (pintype "passive"))
    )
    (net (code "62") (name "/SIG61") (class "Default")
      (node (ref "X1") (pin "B24") (pinfunction "B24_B24") (pintype "passive"))
      (node (ref "X2") (pin "B24") (pinfunction "B24_B24") (pintype "passive"))
      (node (ref "X3") (pin "B24") (pinfunction "B24_B24") (pintype "passive"))
      (node (ref "X4") (pin "B24") (pinfunction "B24_B24") (pintype "passive"))
      (node (ref "X5") (pin "B24") (pinfunction "B24_B24") (pintype "passive"))
      (node (ref "X6") (pin "B24") (pinfunction "B24_B24") (pintype "passive"))
      (node (ref "X7") (pin "B24") (pinfunction "B24_B24") (pintype "passive"))
    )
    (net (code "63") (name "/SIG62") (class "Default")
      (node (ref "X1") (pin "C24") (pinfunction "C24_C24") (pintype "passive"))
      (node (ref "X2") (pin "C24") (pinfunction "C24_C24") (pintype "passive"))
      (node (ref "X3") (pin "C24") (pinfunction "C24_C24") (pintype "passive"))
      (node (ref "X4") (pin "C24") (pinfunction "C24_C24") (pintype "passive"))
      (node (ref "X5") (pin "C24") (pinfunction "C24_C24") (pintype "passive"))
      (node (ref "X6") (pin "C24") (pinfunction "C24_C24") (pintype "passive"))
      (node (ref "X7") (pin "C24") (pinfunction "C24_C24") (pintype "passive"))
    )
    (net (code "64") (name "/SIG63") (class "Default")
      (node (ref "X1") (pin "A25") (pinfunction "A25_A25") (pintype "passive"))
      (node (ref "X2") (pin "A25") (pinfunction "A25_A25") (pintype "passive"))
      (node (ref "X3") (pin "A25") (pinfunction "A25_A25") (pintype "passive"))
      (node (ref "X4") (pin "A25") (pinfunction "A25_A25") (pintype "passive"))
      (node (ref "X5") (pin "A25") (pinfunction "A25_A25") (pintype "passive"))
      (node (ref "X6") (pin "A25") (pinfunction "A25_A25") (pintype "passive"))
      (node (ref "X7") (pin "A25") (pinfunction "A25_A25") (pintype "passive"))
    )
    (net (code "65") (name "/SIG64") (class "Default")
      (node (ref "X1") (pin "B25") (pinfunction "B25_B25") (pintype "passive"))
      (node (ref "X2") (pin "B25") (pinfunction "B25_B25") (pintype "passive"))
      (node (ref "X3") (pin "B25") (pinfunction "B25_B25") (pintype "passive"))
      (node (ref "X4") (pin "B25") (pinfunction "B25_B25") (pintype "passive"))
      (node (ref "X5") (pin "B25") (pinfunction "B25_B25") (pintype "passive"))
      (node (ref "X6") (pin "B25") (pinfunction "B25_B25") (pintype "passive"))
      (node (ref "X7") (pin "B25") (pinfunction "B25_B25") (pintype "passive"))
    )
    (net (code "66") (name "/SIG65") (class "Default")
      (node (ref "X1") (pin "C25") (pinfunction "C25_C25") (pintype "passive"))
      (node (ref "X2") (pin "C25") (pinfunction "C25_C25") (pintype "passive"))
      (node (ref "X3") (pin "C25") (pinfunction "C25_C25") (pintype "passive"))
      (node (ref "X4") (pin "C25") (pinfunction "C25_C25") (pintype "passive"))
      (node (ref "X5") (pin "C25") (pinfunction "C25_C25") (pintype "passive"))
      (node (ref "X6") (pin "C25") (pinfunction "C25_C25") (pintype "passive"))
      (node (ref "X7") (pin "C25") (pinfunction "C25_C25") (pintype "passive"))
    )
    (net (code "67") (name "/SIG66") (class "Default")
      (node (ref "X1") (pin "A26") (pinfunction "A26_A26") (pintype "passive"))
      (node (ref "X2") (pin "A26") (pinfunction "A26_A26") (pintype "passive"))
      (node (ref "X3") (pin "A26") (pinfunction "A26_A26") (pintype "passive"))
      (node (ref "X4") (pin "A26") (pinfunction "A26_A26") (pintype "passive"))
      (node (ref "X5") (pin "A26") (pinfunction "A26_A26") (pintype "passive"))
      (node (ref "X6") (pin "A26") (pinfunction "A26_A26") (pintype "passive"))
      (node (ref "X7") (pin "A26") (pinfunction "A26_A26") (pintype "passive"))
    )
    (net (code "68") (name "/SIG67") (class "Default")
      (node (ref "X1") (pin "B26") (pinfunction "B26_B26") (pintype "passive"))
      (node (ref "X2") (pin "B26") (pinfunction "B26_B26") (pintype "passive"))
      (node (ref "X3") (pin "B26") (pinfunction "B26_B26") (pintype "passive"))
      (node (ref "X4") (pin "B26") (pinfunction "B26_B26") (pintype "passive"))
      (node (ref "X5") (pin "B26") (pinfunction "B26_B26") (pintype "passive"))
      (node (ref "X6") (pin "B26") (pinfunction "B26_B26") (pintype "passive"))
      (node (ref "X7") (pin "B26") (pinfunction "B26_B26") (pintype "passive"))
    )
    (net (code "69") (name "/SIG68") (class "Default")
      (node (ref "X1") (pin "C26") (pinfunction "C26_C26") (pintype "passive"))
      (node (ref "X2") (pin "C26") (pinfunction "C26_C26") (pintype "passive"))
      (node (ref "X3") (pin "C26") (pinfunction "C26_C26") (pintype "passive"))
      (node (ref "X4") (pin "C26") (pinfunction "C26_C26") (pintype "passive"))
      (node (ref "X5") (pin "C26") (pinfunction "C26_C26") (pintype "passive"))
      (node (ref "X6") (pin "C26") (pinfunction "C26_C26") (pintype "passive"))
      (node (ref "X7") (pin "C26") (pinfunction "C26_C26") (pintype "passive"))
    )
    (net (code "70") (name "/SIG69") (class "Default")
      (node (ref "X1") (pin "A27") (pinfunction "A27_A27") (pintype "passive"))
      (node (ref "X2") (pin "A27") (pinfunction "A27_A27") (pintype "passive"))
      (node (ref "X3") (pin "A27") (pinfunction "A27_A27") (pintype "passive"))
      (node (ref "X4") (pin "A27") (pinfunction "A27_A27") (pintype "passive"))
      (node (ref "X5") (pin "A27") (pinfunction "A27_A27") (pintype "passive"))
      (node (ref "X6") (pin "A27") (pinfunction "A27_A27") (pintype "passive"))
      (node (ref "X7") (pin "A27") (pinfunction "A27_A27") (pintype "passive"))
    )
    (net (code "71") (name "/SIG70") (class "Default")
      (node (ref "X1") (pin "B27") (pinfunction "B27_B27") (pintype "passive"))
      (node (ref "X2") (pin "B27") (pinfunction "B27_B27") (pintype "passive"))
      (node (ref "X3") (pin "B27") (pinfunction "B27_B27") (pintype "passive"))
      (node (ref "X4") (pin "B27") (pinfunction "B27_B27") (pintype "passive"))
      (node (ref "X5") (pin "B27") (pinfunction "B27_B27") (pintype "passive"))
      (node (ref "X6") (pin "B27") (pinfunction "B27_B27") (pintype "passive"))
      (node (ref "X7") (pin "B27") (pinfunction "B27_B27") (pintype "passive"))
    )
    (net (code "72") (name "/SIG71") (class "Default")
      (node (ref "X1") (pin "C27") (pinfunction "C27_C27") (pintype "passive"))
      (node (ref "X2") (pin "C27") (pinfunction "C27_C27") (pintype "passive"))
      (node (ref "X3") (pin "C27") (pinfunction "C27_C27") (pintype "passive"))
      (node (ref "X4") (pin "C27") (pinfunction "C27_C27") (pintype "passive"))
      (node (ref "X5") (pin "C27") (pinfunction "C27_C27") (pintype "passive"))
      (node (ref "X6") (pin "C27") (pinfunction "C27_C27") (pintype "passive"))
      (node (ref "X7") (pin "C27") (pinfunction "C27_C27") (pintype "passive"))
    )
    (net (code "73") (name "/SIG72") (class "Default")
      (node (ref "X1") (pin "A28") (pinfunction "A28_A28") (pintype "passive"))
      (node (ref "X2") (pin "A28") (pinfunction "A28_A28") (pintype "passive"))
      (node (ref "X3") (pin "A28") (pinfunction "A28_A28") (pintype "passive"))
      (node (ref "X4") (pin "A28") (pinfunction "A28_A28") (pintype "passive"))
      (node (ref "X5") (pin "A28") (pinfunction "A28_A28") (pintype "passive"))
      (node (ref "X6") (pin "A28") (pinfunction "A28_A28") (pintype "passive"))
      (node (ref "X7") (pin "A28") (pinfunction "A28_A28") (pintype "passive"))
    )
    (net (code "74") (name "/SIG73") (class "Default")
      (node (ref "X1") (pin "B28") (pinfunction "B28_B28") (pintype "passive"))
      (node (ref "X2") (pin "B28") (pinfunction "B28_B28") (pintype "passive"))
      (node (ref "X3") (pin "B28") (pinfunction "B28_B28") (pintype "passive"))
      (node (ref "X4") (pin "B28") (pinfunction "B28_B28") (pintype "passive"))
      (node (ref "X5") (pin "B28") (pinfunction "B28_B28") (pintype "passive"))
      (node (ref "X6") (pin "B28") (pinfunction "B28_B28") (pintype "passive"))
      (node (ref "X7") (pin "B28") (pinfunction "B28_B28") (pintype "passive"))
    )
    (net (code "75") (name "/SIG74") (class "Default")
      (node (ref "X1") (pin "C28") (pinfunction "C28_C28") (pintype "passive"))
      (node (ref "X2") (pin "C28") (pinfunction "C28_C28") (pintype "passive"))
      (node (ref "X3") (pin "C28") (pinfunction "C28_C28") (pintype "passive"))
      (node (ref "X4") (pin "C28") (pinfunction "C28_C28") (pintype "passive"))
      (node (ref "X5") (pin "C28") (pinfunction "C28_C28") (pintype "passive"))
      (node (ref "X6") (pin "C28") (pinfunction "C28_C28") (pintype "passive"))
      (node (ref "X7") (pin "C28") (pinfunction "C28_C28") (pintype "passive"))
    )
    (net (code "76") (name "/SIG75") (class "Default")
      (node (ref "X1") (pin "A29") (pinfunction "A29_A29") (pintype "passive"))
      (node (ref "X2") (pin "A29") (pinfunction "A29_A29") (pintype "passive"))
      (node (ref "X3") (pin "A29") (pinfunction "A29_A29") (pintype "passive"))
      (node (ref "X4") (pin "A29") (pinfunction "A29_A29") (pintype "passive"))
      (node (ref "X5") (pin "A29") (pinfunction "A29_A29") (pintype "passive"))
      (node (ref "X6") (pin "A29") (pinfunction "A29_A29") (pintype "passive"))
      (node (ref "X7") (pin "A29") (pinfunction "A29_A29") (pintype "passive"))
    )
    (net (code "77") (name "/SIG76") (class "Default")
      (node (ref "X1") (pin "B29") (pinfunction "B29_B29") (pintype "passive"))
      (node (ref "X2") (pin "B29") (pinfunction "B29_B29") (pintype "passive"))
      (node (ref "X3") (pin "B29") (pinfunction "B29_B29") (pintype "passive"))
      (node (ref "X4") (pin "B29") (pinfunction "B29_B29") (pintype "passive"))
      (node (ref "X5") (pin "B29") (pinfunction "B29_B29") (pintype "passive"))
      (node (ref "X6") (pin "B29") (pinfunction "B29_B29") (pintype "passive"))
      (node (ref "X7") (pin "B29") (pinfunction "B29_B29") (pintype "passive"))
    )
    (net (code "78") (name "/SIG77") (class "Default")
      (node (ref "X1") (pin "C29") (pinfunction "C29_C29") (pintype "passive"))
      (node (ref "X2") (pin "C29") (pinfunction "C29_C29") (pintype "passive"))
      (node (ref "X3") (pin "C29") (pinfunction "C29_C29") (pintype "passive"))
      (node (ref "X4") (pin "C29") (pinfunction "C29_C29") (pintype "passive"))
      (node (ref "X5") (pin "C29") (pinfunction "C29_C29") (pintype "passive"))
      (node (ref "X6") (pin "C29") (pinfunction "C29_C29") (pintype "passive"))
      (node (ref "X7") (pin "C29") (pinfunction "C29_C29") (pintype "passive"))
    )
    (net (code "79") (name "/SIG78") (class "Default")
      (node (ref "X1") (pin "A30") (pinfunction "A30_A30") (pintype "passive"))
      (node (ref "X2") (pin "A30") (pinfunction "A30_A30") (pintype "passive"))
      (node (ref "X3") (pin "A30") (pinfunction "A30_A30") (pintype "passive"))
      (node (ref "X4") (pin "A30") (pinfunction "A30_A30") (pintype "passive"))
      (node (ref "X5") (pin "A30") (pinfunction "A30_A30") (pintype "passive"))
      (node (ref "X6") (pin "A30") (pinfunction "A30_A30") (pintype "passive"))
      (node (ref "X7") (pin "A30") (pinfunction "A30_A30") (pintype "passive"))
    )
    (net (code "80") (name "/SIG79") (class "Default")
      (node (ref "X1") (pin "B30") (pinfunction "B30_B30") (pintype "passive"))
      (node (ref "X2") (pin "B30") (pinfunction "B30_B30") (pintype "passive"))
      (node (ref "X3") (pin "B30") (pinfunction "B30_B30") (pintype "passive"))
      (node (ref "X4") (pin "B30") (pinfunction "B30_B30") (pintype "passive"))
      (node (ref "X5") (pin "B30") (pinfunction "B30_B30") (pintype "passive"))
      (node (ref "X6") (pin "B30") (pinfunction "B30_B30") (pintype "passive"))
      (node (ref "X7") (pin "B30") (pinfunction "B30_B30") (pintype "passive"))
    )
    (net (code "81") (name "/SIG80") (class "Default")
      (node (ref "X1") (pin "C30") (pinfunction "C30_C30") (pintype "passive"))
      (node (ref "X2") (pin "C30") (pinfunction "C30_C30") (pintype "passive"))
      (node (ref "X3") (pin "C30") (pinfunction "C30_C30") (pintype "passive"))
      (node (ref "X4") (pin "C30") (pinfunction "C30_C30") (pintype "passive"))
      (node (ref "X5") (pin "C30") (pinfunction "C30_C30") (pintype "passive"))
      (node (ref "X6") (pin "C30") (pinfunction "C30_C30") (pintype "passive"))
      (node (ref "X7") (pin "C30") (pinfunction "C30_C30") (pintype "passive"))
    )
    (net (code "82") (name "5V") (class "Default")
      (node (ref "5V") (pin "1") (pinfunction "P_1") (pintype "passive"))
      (node (ref "R1") (pin "2") (pinfunction "2_2") (pintype "passive"))
      (node (ref "X1") (pin "A2") (pinfunction "A2_A2") (pintype "passive"))
      (node (ref "X1") (pin "A31") (pinfunction "A31_A31") (pintype "passive"))
      (node (ref "X1") (pin "B2") (pinfunction "B2_B2") (pintype "passive"))
      (node (ref "X1") (pin "B31") (pinfunction "B31_B31") (pintype "passive"))
      (node (ref "X1") (pin "C2") (pinfunction "C2_C2") (pintype "passive"))
      (node (ref "X1") (pin "C31") (pinfunction "C31_C31") (pintype "passive"))
      (node (ref "X2") (pin "A2") (pinfunction "A2_A2") (pintype "passive"))
      (node (ref "X2") (pin "A31") (pinfunction "A31_A31") (pintype "passive"))
      (node (ref "X2") (pin "B2") (pinfunction "B2_B2") (pintype "passive"))
      (node (ref "X2") (pin "B31") (pinfunction "B31_B31") (pintype "passive"))
      (node (ref "X2") (pin "C2") (pinfunction "C2_C2") (pintype "passive"))
      (node (ref "X2") (pin "C31") (pinfunction "C31_C31") (pintype "passive"))
      (node (ref "X3") (pin "A2") (pinfunction "A2_A2") (pintype "passive"))
      (node (ref "X3") (pin "A31") (pinfunction "A31_A31") (pintype "passive"))
      (node (ref "X3") (pin "B2") (pinfunction "B2_B2") (pintype "passive"))
      (node (ref "X3") (pin "B31") (pinfunction "B31_B31") (pintype "passive"))
      (node (ref "X3") (pin "C2") (pinfunction "C2_C2") (pintype "passive"))
      (node (ref "X3") (pin "C31") (pinfunction "C31_C31") (pintype "passive"))
      (node (ref "X4") (pin "A2") (pinfunction "A2_A2") (pintype "passive"))
      (node (ref "X4") (pin "A31") (pinfunction "A31_A31") (pintype "passive"))
      (node (ref "X4") (pin "B2") (pinfunction "B2_B2") (pintype "passive"))
      (node (ref "X4") (pin "B31") (pinfunction "B31_B31") (pintype "passive"))
      (node (ref "X4") (pin "C2") (pinfunction "C2_C2") (pintype "passive"))
      (node (ref "X4") (pin "C31") (pinfunction "C31_C31") (pintype "passive"))
      (node (ref "X5") (pin "A2") (pinfunction "A2_A2") (pintype "passive"))
      (node (ref "X5") (pin "A31") (pinfunction "A31_A31") (pintype "passive"))
      (node (ref "X5") (pin "B2") (pinfunction "B2_B2") (pintype "passive"))
      (node (ref "X5") (pin "B31") (pinfunction "B31_B31") (pintype "passive"))
      (node (ref "X5") (pin "C2") (pinfunction "C2_C2") (pintype "passive"))
      (node (ref "X5") (pin "C31") (pinfunction "C31_C31") (pintype "passive"))
      (node (ref "X6") (pin "A2") (pinfunction "A2_A2") (pintype "passive"))
      (node (ref "X6") (pin "A31") (pinfunction "A31_A31") (pintype "passive"))
      (node (ref "X6") (pin "B2") (pinfunction "B2_B2") (pintype "passive"))
      (node (ref "X6") (pin "B31") (pinfunction "B31_B31") (pintype "passive"))
      (node (ref "X6") (pin "C2") (pinfunction "C2_C2") (pintype "passive"))
      (node (ref "X6") (pin "C31") (pinfunction "C31_C31") (pintype "passive"))
      (node (ref "X7") (pin "A2") (pinfunction "A2_A2") (pintype "passive"))
      (node (ref "X7") (pin "A31") (pinfunction "A31_A31") (pintype "passive"))
      (node (ref "X7") (pin "B2") (pinfunction "B2_B2") (pintype "passive"))
      (node (ref "X7") (pin "B31") (pinfunction "B31_B31") (pintype "passive"))
      (node (ref "X7") (pin "C2") (pinfunction "C2_C2") (pintype "passive"))
      (node (ref "X7") (pin "C31") (pinfunction "C31_C31") (pintype "passive"))
    )
    (net (code "83") (name "12V") (class "Default")
      (node (ref "12V") (pin "1") (pinfunction "P_1") (pintype "passive"))
      (node (ref "X1") (pin "A3") (pinfunction "A3_A3") (pintype "passive"))
      (node (ref "X1") (pin "B3") (pinfunction "B3_B3") (pintype "passive"))
      (node (ref "X1") (pin "C3") (pinfunction "C3_C3") (pintype "passive"))
      (node (ref "X2") (pin "A3") (pinfunction "A3_A3") (pintype "passive"))
      (node (ref "X2") (pin "B3") (pinfunction "B3_B3") (pintype "passive"))
      (node (ref "X2") (pin "C3") (pinfunction "C3_C3") (pintype "passive"))
      (node (ref "X3") (pin "A3") (pinfunction "A3_A3") (pintype "passive"))
      (node (ref "X3") (pin "B3") (pinfunction "B3_B3") (pintype "passive"))
      (node (ref "X3") (pin "C3") (pinfunction "C3_C3") (pintype "passive"))
      (node (ref "X4") (pin "A3") (pinfunction "A3_A3") (pintype "passive"))
      (node (ref "X4") (pin "B3") (pinfunction "B3_B3") (pintype "passive"))
      (node (ref "X4") (pin "C3") (pinfunction "C3_C3") (pintype "passive"))
      (node (ref "X5") (pin "A3") (pinfunction "A3_A3") (pintype "passive"))
      (node (ref "X5") (pin "B3") (pinfunction "B3_B3") (pintype "passive"))
      (node (ref "X5") (pin "C3") (pinfunction "C3_C3") (pintype "passive"))
      (node (ref "X6") (pin "A3") (pinfunction "A3_A3") (pintype "passive"))
      (node (ref "X6") (pin "B3") (pinfunction "B3_B3") (pintype "passive"))
      (node (ref "X6") (pin "C3") (pinfunction "C3_C3") (pintype "passive"))
      (node (ref "X7") (pin "A3") (pinfunction "A3_A3") (pintype "passive"))
      (node (ref "X7") (pin "B3") (pinfunction "B3_B3") (pintype "passive"))
      (node (ref "X7") (pin "C3") (pinfunction "C3_C3") (pintype "passive"))
    )
    (net (code "84") (name "GND") (class "Default")
      (node (ref "GND") (pin "1") (pinfunction "P_1") (pintype "passive"))
      (node (ref "LED1") (pin "K") (pinfunction "C_K") (pintype "passive"))
      (node (ref "X1") (pin "A1") (pinfunction "A1_A1") (pintype "passive"))
      (node (ref "X1") (pin "A32") (pinfunction "A32_A32") (pintype "passive"))
      (node (ref "X1") (pin "B1") (pinfunction "B1_B1") (pintype "passive"))
      (node (ref "X1") (pin "B32") (pinfunction "B32_B32") (pintype "passive"))
      (node (ref "X1") (pin "C1") (pinfunction "C1_C1") (pintype "passive"))
      (node (ref "X1") (pin "C32") (pinfunction "C32_C32") (pintype "passive"))
      (node (ref "X2") (pin "A1") (pinfunction "A1_A1") (pintype "passive"))
      (node (ref "X2") (pin "A32") (pinfunction "A32_A32") (pintype "passive"))
      (node (ref "X2") (pin "B1") (pinfunction "B1_B1") (pintype "passive"))
      (node (ref "X2") (pin "B32") (pinfunction "B32_B32") (pintype "passive"))
      (node (ref "X2") (pin "C1") (pinfunction "C1_C1") (pintype "passive"))
      (node (ref "X2") (pin "C32") (pinfunction "C32_C32") (pintype "passive"))
      (node (ref "X3") (pin "A1") (pinfunction "A1_A1") (pintype "passive"))
      (node (ref "X3") (pin "A32") (pinfunction "A32_A32") (pintype "passive"))
      (node (ref "X3") (pin "B1") (pinfunction "B1_B1") (pintype "passive"))
      (node (ref "X3") (pin "B32") (pinfunction "B32_B32") (pintype "passive"))
      (node (ref "X3") (pin "C1") (pinfunction "C1_C1") (pintype "passive"))
      (node (ref "X3") (pin "C32") (pinfunction "C32_C32") (pintype "passive"))
      (node (ref "X4") (pin "A1") (pinfunction "A1_A1") (pintype "passive"))
      (node (ref "X4") (pin "A32") (pinfunction "A32_A32") (pintype "passive"))
      (node (ref "X4") (pin "B1") (pinfunction "B1_B1") (pintype "passive"))
      (node (ref "X4") (pin "B32") (pinfunction "B32_B32") (pintype "passive"))
      (node (ref "X4") (pin "C1") (pinfunction "C1_C1") (pintype "passive"))
      (node (ref "X4") (pin "C32") (pinfunction "C32_C32") (pintype "passive"))
      (node (ref "X5") (pin "A1") (pinfunction "A1_A1") (pintype "passive"))
      (node (ref "X5") (pin "A32") (pinfunction "A32_A32") (pintype "passive"))
      (node (ref "X5") (pin "B1") (pinfunction "B1_B1") (pintype "passive"))
      (node (ref "X5") (pin "B32") (pinfunction "B32_B32") (pintype "passive"))
      (node (ref "X5") (pin "C1") (pinfunction "C1_C1") (pintype "passive"))
      (node (ref "X5") (pin "C32") (pinfunction "C32_C32") (pintype "passive"))
      (node (ref "X6") (pin "A1") (pinfunction "A1_A1") (pintype "passive"))
      (node (ref "X6") (pin "A32") (pinfunction "A32_A32") (pintype "passive"))
      (node (ref "X6") (pin "B1") (pinfunction "B1_B1") (pintype "passive"))
      (node (ref "X6") (pin "B32") (pinfunction "B32_B32") (pintype "passive"))
      (node (ref "X6") (pin "C1") (pinfunction "C1_C1") (pintype "passive"))
      (node (ref "X6") (pin "C32") (pinfunction "C32_C32") (pintype "passive"))
      (node (ref "X7") (pin "A1") (pinfunction "A1_A1") (pintype "passive"))
      (node (ref "X7") (pin "A32") (pinfunction "A32_A32") (pintype "passive"))
      (node (ref "X7") (pin "B1") (pinfunction "B1_B1") (pintype "passive"))
      (node (ref "X7") (pin "B32") (pinfunction "B32_B32") (pintype "passive"))
      (node (ref "X7") (pin "C1") (pinfunction "C1_C1") (pintype "passive"))
      (node (ref "X7") (pin "C32") (pinfunction "C32_C32") (pintype "passive"))
    )
    (net (code "85") (name "Net-(LED1-PadA)") (class "Default")
      (node (ref "LED1") (pin "A") (pinfunction "A_A") (pintype "passive"))
      (node (ref "R1") (pin "1") (pinfunction "1_1") (pintype "passive"))
    )
  )
)
